# PulseOxi.net
KiCad netlist of a schematic drawn in EAGLE
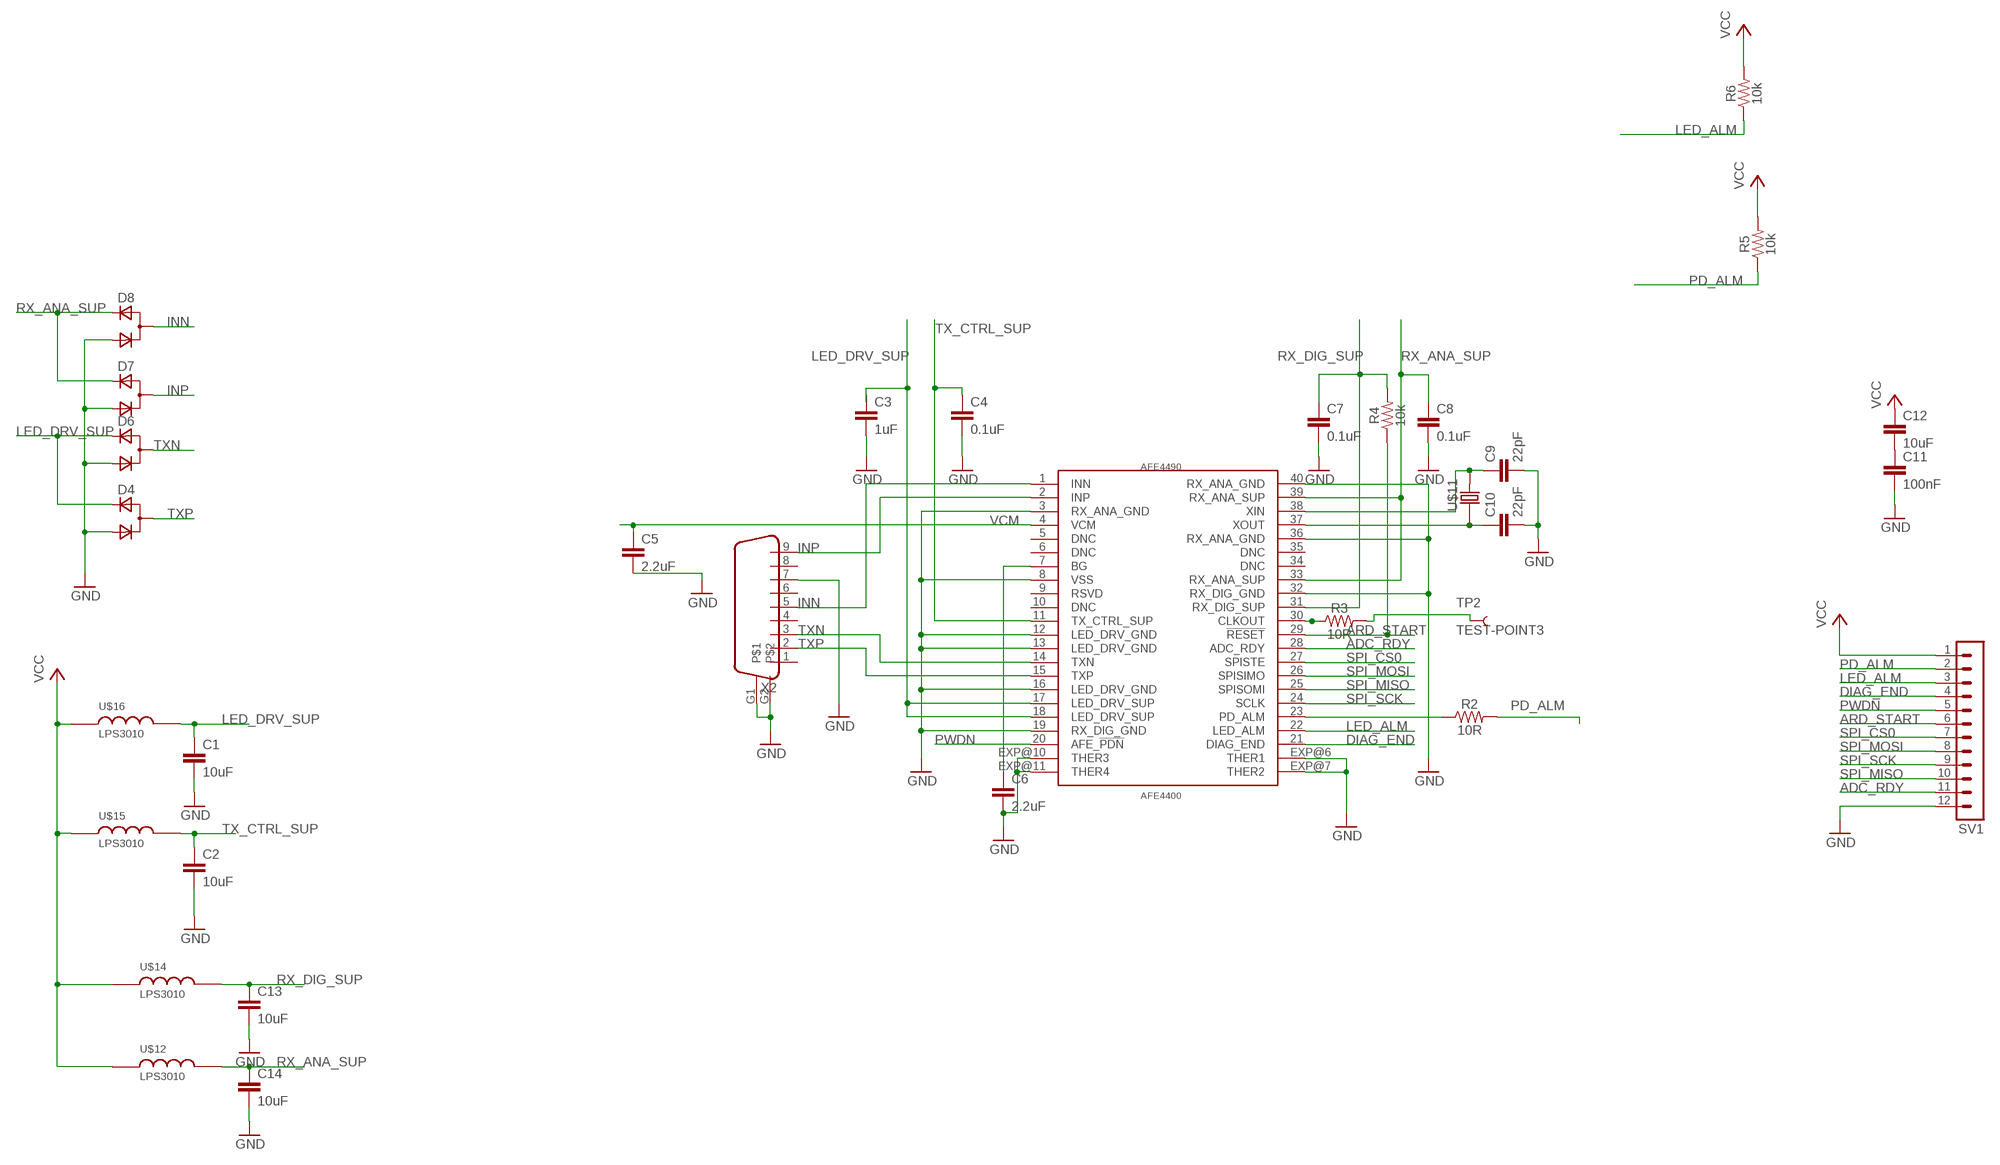
[diagram p0: schematic, sheet 1]

(export (version "E")
  (design (tool "Eeschema 10.0.6"))
  (components
    (comp (ref "AFE4490")
      (value "AFE4400")
      (footprint "eagle-import:QFN-40")
      (libsource (lib "eagle-import") (part "AFE4400"))
    )
    (comp (ref "C1")
      (value "10uF")
      (footprint "eagle-import:0603")
      (libsource (lib "eagle-import") (part "27PF-0603-50V-5%"))
    )
    (comp (ref "C2")
      (value "10uF")
      (footprint "eagle-import:0603")
      (libsource (lib "eagle-import") (part "27PF-0603-50V-5%"))
    )
    (comp (ref "C3")
      (value "1uF")
      (footprint "eagle-import:0603")
      (libsource (lib "eagle-import") (part "27PF-0603-50V-5%"))
    )
    (comp (ref "C4")
      (value "0.1uF")
      (footprint "eagle-import:0603")
      (libsource (lib "eagle-import") (part "27PF-0603-50V-5%"))
    )
    (comp (ref "C5")
      (value "2.2uF")
      (footprint "eagle-import:0603")
      (libsource (lib "eagle-import") (part "27PF-0603-50V-5%"))
    )
    (comp (ref "C6")
      (value "2.2uF")
      (footprint "eagle-import:0603")
      (libsource (lib "eagle-import") (part "27PF-0603-50V-5%"))
    )
    (comp (ref "C7")
      (value "0.1uF")
      (footprint "eagle-import:0603")
      (libsource (lib "eagle-import") (part "27PF-0603-50V-5%"))
    )
    (comp (ref "C8")
      (value "0.1uF")
      (footprint "eagle-import:0603")
      (libsource (lib "eagle-import") (part "27PF-0603-50V-5%"))
    )
    (comp (ref "C9")
      (value "22pF")
      (footprint "eagle-import:0603")
      (libsource (lib "eagle-import") (part "27PF-0603-50V-5%"))
    )
    (comp (ref "C10")
      (value "22pF")
      (footprint "eagle-import:0603")
      (libsource (lib "eagle-import") (part "27PF-0603-50V-5%"))
    )
    (comp (ref "C11")
      (value "100nF")
      (footprint "eagle-import:0603")
      (libsource (lib "eagle-import") (part "27PF-0603-50V-5%"))
    )
    (comp (ref "C12")
      (value "10uF")
      (footprint "eagle-import:0603")
      (libsource (lib "eagle-import") (part "27PF-0603-50V-5%"))
    )
    (comp (ref "C13")
      (value "10uF")
      (footprint "eagle-import:0603")
      (libsource (lib "eagle-import") (part "27PF-0603-50V-5%"))
    )
    (comp (ref "C14")
      (value "10uF")
      (footprint "eagle-import:0603")
      (libsource (lib "eagle-import") (part "27PF-0603-50V-5%"))
    )
    (comp (ref "D4")
      (value "D_ACACSOT323")
      (footprint "eagle-import:SOT323")
      (libsource (lib "eagle-import") (part "D_ACACSOT323"))
    )
    (comp (ref "D6")
      (value "D_ACACSOT323")
      (footprint "eagle-import:SOT323")
      (libsource (lib "eagle-import") (part "D_ACACSOT323"))
    )
    (comp (ref "D7")
      (value "D_ACACSOT323")
      (footprint "eagle-import:SOT323")
      (libsource (lib "eagle-import") (part "D_ACACSOT323"))
    )
    (comp (ref "D8")
      (value "D_ACACSOT323")
      (footprint "eagle-import:SOT323")
      (libsource (lib "eagle-import") (part "D_ACACSOT323"))
    )
    (comp (ref "R2")
      (value "10R")
      (footprint "eagle-import:0603")
      (libsource (lib "eagle-import") (part "1.8MOHM"))
    )
    (comp (ref "R3")
      (value "10R")
      (footprint "eagle-import:0603")
      (libsource (lib "eagle-import") (part "1.8MOHM"))
    )
    (comp (ref "R4")
      (value "10k")
      (footprint "eagle-import:0603")
      (libsource (lib "eagle-import") (part "1.8MOHM"))
    )
    (comp (ref "R5")
      (value "10k")
      (footprint "eagle-import:0603")
      (libsource (lib "eagle-import") (part "1.8MOHM"))
    )
    (comp (ref "R6")
      (value "10k")
      (footprint "eagle-import:0603")
      (libsource (lib "eagle-import") (part "1.8MOHM"))
    )
    (comp (ref "SV1")
      (value "MA12-1")
      (footprint "eagle-import:MA12-1")
      (libsource (lib "eagle-import") (part "MA12-1"))
    )
    (comp (ref "TP2")
      (value "TEST-POINT3")
      (footprint "eagle-import:PAD.03X.03")
      (libsource (lib "eagle-import") (part "TEST-POINT3"))
    )
    (comp (ref "U$11")
      (value "ABM3")
      (footprint "eagle-import:ABM3")
      (libsource (lib "eagle-import") (part "ABM3"))
    )
    (comp (ref "U$12")
      (value "LPS3010")
      (footprint "eagle-import:LPS")
      (libsource (lib "eagle-import") (part "LPS"))
    )
    (comp (ref "U$14")
      (value "LPS3010")
      (footprint "eagle-import:LPS")
      (libsource (lib "eagle-import") (part "LPS"))
    )
    (comp (ref "U$15")
      (value "LPS3010")
      (footprint "eagle-import:LPS")
      (libsource (lib "eagle-import") (part "LPS"))
    )
    (comp (ref "U$16")
      (value "LPS3010")
      (footprint "eagle-import:LPS")
      (libsource (lib "eagle-import") (part "LPS"))
    )
    (comp (ref "X2")
      (value "DB9")
      (footprint "eagle-import:DB9")
      (libsource (lib "eagle-import") (part "DB9"))
    )
  )
  (nets
    (net (code "1") (name "/ADC_RDY") (class "Default")
      (node (ref "AFE4490") (pin "28") (pinfunction "ADC_RDY_28") (pintype "bidirectional"))
      (node (ref "SV1") (pin "11") (pinfunction "11_11") (pintype "passive"))
    )
    (net (code "2") (name "/ARD_START") (class "Default")
      (node (ref "AFE4490") (pin "29") (pinfunction "~{RESET}_29") (pintype "bidirectional"))
      (node (ref "R4") (pin "1") (pinfunction "1_1") (pintype "passive"))
      (node (ref "SV1") (pin "6") (pinfunction "6_6") (pintype "passive"))
    )
    (net (code "3") (name "/DIAG_END") (class "Default")
      (node (ref "AFE4490") (pin "21") (pinfunction "DIAG_END_21") (pintype "bidirectional"))
      (node (ref "SV1") (pin "4") (pinfunction "4_4") (pintype "passive"))
    )
    (net (code "4") (name "/INN") (class "Default")
      (node (ref "AFE4490") (pin "1") (pinfunction "INN_1") (pintype "bidirectional"))
      (node (ref "D8") (pin "1") (pinfunction "CA_1") (pintype "passive"))
      (node (ref "X2") (pin "5") (pinfunction "5_5") (pintype "passive"))
    )
    (net (code "5") (name "/INP") (class "Default")
      (node (ref "AFE4490") (pin "2") (pinfunction "INP_2") (pintype "bidirectional"))
      (node (ref "D7") (pin "1") (pinfunction "CA_1") (pintype "passive"))
      (node (ref "X2") (pin "9") (pinfunction "9_9") (pintype "passive"))
    )
    (net (code "6") (name "/LED_ALM") (class "Default")
      (node (ref "AFE4490") (pin "22") (pinfunction "LED_ALM_22") (pintype "bidirectional"))
      (node (ref "R6") (pin "1") (pinfunction "1_1") (pintype "passive"))
      (node (ref "SV1") (pin "3") (pinfunction "3_3") (pintype "passive"))
    )
    (net (code "7") (name "/LED_DRV_SUP") (class "Default")
      (node (ref "AFE4490") (pin "17") (pinfunction "LED_DRV_SUP_17") (pintype "bidirectional"))
      (node (ref "AFE4490") (pin "18") (pinfunction "LED_DRV_SUP_18") (pintype "bidirectional"))
      (node (ref "C1") (pin "1") (pinfunction "1_1") (pintype "passive"))
      (node (ref "C3") (pin "1") (pinfunction "1_1") (pintype "passive"))
      (node (ref "D4") (pin "3") (pinfunction "A_3") (pintype "passive"))
      (node (ref "D6") (pin "3") (pinfunction "A_3") (pintype "passive"))
      (node (ref "U$16") (pin "2") (pinfunction "P$2_2") (pintype "bidirectional"))
    )
    (net (code "8") (name "/PD_ALM") (class "Default")
      (node (ref "R2") (pin "2") (pinfunction "2_2") (pintype "passive"))
      (node (ref "R5") (pin "1") (pinfunction "1_1") (pintype "passive"))
      (node (ref "SV1") (pin "2") (pinfunction "2_2") (pintype "passive"))
    )
    (net (code "9") (name "/PWDN") (class "Default")
      (node (ref "AFE4490") (pin "20") (pinfunction "AFE_~{PDN}_20") (pintype "bidirectional"))
      (node (ref "SV1") (pin "5") (pinfunction "5_5") (pintype "passive"))
    )
    (net (code "10") (name "/RX_ANA_SUP") (class "Default")
      (node (ref "AFE4490") (pin "33") (pinfunction "RX_ANA_SUP_33") (pintype "bidirectional"))
      (node (ref "AFE4490") (pin "39") (pinfunction "RX_ANA_SUP_39") (pintype "bidirectional"))
      (node (ref "C14") (pin "1") (pinfunction "1_1") (pintype "passive"))
      (node (ref "C8") (pin "1") (pinfunction "1_1") (pintype "passive"))
      (node (ref "D7") (pin "3") (pinfunction "A_3") (pintype "passive"))
      (node (ref "D8") (pin "3") (pinfunction "A_3") (pintype "passive"))
      (node (ref "U$12") (pin "2") (pinfunction "P$2_2") (pintype "bidirectional"))
    )
    (net (code "11") (name "/RX_DIG_SUP") (class "Default")
      (node (ref "AFE4490") (pin "31") (pinfunction "RX_DIG_SUP_31") (pintype "bidirectional"))
      (node (ref "C13") (pin "1") (pinfunction "1_1") (pintype "passive"))
      (node (ref "C7") (pin "1") (pinfunction "1_1") (pintype "passive"))
      (node (ref "R4") (pin "2") (pinfunction "2_2") (pintype "passive"))
      (node (ref "U$14") (pin "2") (pinfunction "P$2_2") (pintype "bidirectional"))
    )
    (net (code "12") (name "/SPI_CS0") (class "Default")
      (node (ref "AFE4490") (pin "27") (pinfunction "SPISTE_27") (pintype "bidirectional"))
      (node (ref "SV1") (pin "7") (pinfunction "7_7") (pintype "passive"))
    )
    (net (code "13") (name "/SPI_MISO") (class "Default")
      (node (ref "AFE4490") (pin "25") (pinfunction "SPISOMI_25") (pintype "bidirectional"))
      (node (ref "SV1") (pin "10") (pinfunction "10_10") (pintype "passive"))
    )
    (net (code "14") (name "/SPI_MOSI") (class "Default")
      (node (ref "AFE4490") (pin "26") (pinfunction "SPISIMO_26") (pintype "bidirectional"))
      (node (ref "SV1") (pin "8") (pinfunction "8_8") (pintype "passive"))
    )
    (net (code "15") (name "/SPI_SCK") (class "Default")
      (node (ref "AFE4490") (pin "24") (pinfunction "SCLK_24") (pintype "bidirectional"))
      (node (ref "SV1") (pin "9") (pinfunction "9_9") (pintype "passive"))
    )
    (net (code "16") (name "/TXN") (class "Default")
      (node (ref "AFE4490") (pin "14") (pinfunction "TXN_14") (pintype "bidirectional"))
      (node (ref "D6") (pin "1") (pinfunction "CA_1") (pintype "passive"))
      (node (ref "X2") (pin "3") (pinfunction "3_3") (pintype "passive"))
    )
    (net (code "17") (name "/TXP") (class "Default")
      (node (ref "AFE4490") (pin "15") (pinfunction "TXP_15") (pintype "bidirectional"))
      (node (ref "D4") (pin "1") (pinfunction "CA_1") (pintype "passive"))
      (node (ref "X2") (pin "2") (pinfunction "2_2") (pintype "passive"))
    )
    (net (code "18") (name "/TX_CTRL_SUP") (class "Default")
      (node (ref "AFE4490") (pin "11") (pinfunction "TX_CTRL_SUP_11") (pintype "bidirectional"))
      (node (ref "C2") (pin "1") (pinfunction "1_1") (pintype "passive"))
      (node (ref "C4") (pin "1") (pinfunction "1_1") (pintype "passive"))
      (node (ref "U$15") (pin "2") (pinfunction "P$2_2") (pintype "bidirectional"))
    )
    (net (code "19") (name "/VCM") (class "Default")
      (node (ref "AFE4490") (pin "4") (pinfunction "VCM_4") (pintype "bidirectional"))
      (node (ref "C5") (pin "1") (pinfunction "1_1") (pintype "passive"))
    )
    (net (code "20") (name "GND") (class "Default")
      (node (ref "AFE4490") (pin "12") (pinfunction "LED_DRV_GND_12") (pintype "bidirectional"))
      (node (ref "AFE4490") (pin "13") (pinfunction "LED_DRV_GND_13") (pintype "bidirectional"))
      (node (ref "AFE4490") (pin "16") (pinfunction "LED_DRV_GND_16") (pintype "bidirectional"))
      (node (ref "AFE4490") (pin "19") (pinfunction "RX_DIG_GND_19") (pintype "bidirectional"))
      (node (ref "AFE4490") (pin "3") (pinfunction "RX_ANA_GND_3") (pintype "bidirectional"))
      (node (ref "AFE4490") (pin "32") (pinfunction "RX_DIG_GND_32") (pintype "bidirectional"))
      (node (ref "AFE4490") (pin "36") (pinfunction "RX_ANA_GND_36") (pintype "bidirectional"))
      (node (ref "AFE4490") (pin "40") (pinfunction "RX_ANA_GND_40") (pintype "bidirectional"))
      (node (ref "AFE4490") (pin "8") (pinfunction "VSS_8") (pintype "bidirectional"))
      (node (ref "AFE4490") (pin "EXP@10") (pinfunction "THER3_EXP@10") (pintype "bidirectional"))
      (node (ref "AFE4490") (pin "EXP@11") (pinfunction "THER4_EXP@11") (pintype "bidirectional"))
      (node (ref "AFE4490") (pin "EXP@6") (pinfunction "THER1_EXP@6") (pintype "bidirectional"))
      (node (ref "AFE4490") (pin "EXP@7") (pinfunction "THER2_EXP@7") (pintype "bidirectional"))
      (node (ref "C1") (pin "2") (pinfunction "2_2") (pintype "passive"))
      (node (ref "C10") (pin "2") (pinfunction "2_2") (pintype "passive"))
      (node (ref "C11") (pin "2") (pinfunction "2_2") (pintype "passive"))
      (node (ref "C13") (pin "2") (pinfunction "2_2") (pintype "passive"))
      (node (ref "C14") (pin "2") (pinfunction "2_2") (pintype "passive"))
      (node (ref "C2") (pin "2") (pinfunction "2_2") (pintype "passive"))
      (node (ref "C3") (pin "2") (pinfunction "2_2") (pintype "passive"))
      (node (ref "C4") (pin "2") (pinfunction "2_2") (pintype "passive"))
      (node (ref "C5") (pin "2") (pinfunction "2_2") (pintype "passive"))
      (node (ref "C6") (pin "2") (pinfunction "2_2") (pintype "passive"))
      (node (ref "C7") (pin "2") (pinfunction "2_2") (pintype "passive"))
      (node (ref "C8") (pin "2") (pinfunction "2_2") (pintype "passive"))
      (node (ref "C9") (pin "2") (pinfunction "2_2") (pintype "passive"))
      (node (ref "D4") (pin "2") (pinfunction "C_2") (pintype "passive"))
      (node (ref "D6") (pin "2") (pinfunction "C_2") (pintype "passive"))
      (node (ref "D7") (pin "2") (pinfunction "C_2") (pintype "passive"))
      (node (ref "D8") (pin "2") (pinfunction "C_2") (pintype "passive"))
      (node (ref "SV1") (pin "12") (pinfunction "12_12") (pintype "passive"))
      (node (ref "X2") (pin "7") (pinfunction "7_7") (pintype "passive"))
      (node (ref "X2") (pin "G1") (pinfunction "P$1_G1") (pintype "bidirectional"))
      (node (ref "X2") (pin "G2") (pinfunction "P$2_G2") (pintype "bidirectional"))
    )
    (net (code "21") (name "Net-(AFE4490-BG)") (class "Default")
      (node (ref "AFE4490") (pin "7") (pinfunction "BG_7") (pintype "bidirectional"))
      (node (ref "C6") (pin "1") (pinfunction "1_1") (pintype "passive"))
    )
    (net (code "22") (name "Net-(AFE4490-CLKOUT)") (class "Default")
      (node (ref "AFE4490") (pin "30") (pinfunction "CLKOUT_30") (pintype "bidirectional"))
      (node (ref "R3") (pin "1") (pinfunction "1_1") (pintype "passive"))
    )
    (net (code "23") (name "Net-(AFE4490-PD_ALM)") (class "Default")
      (node (ref "AFE4490") (pin "23") (pinfunction "PD_ALM_23") (pintype "bidirectional"))
      (node (ref "R2") (pin "1") (pinfunction "1_1") (pintype "passive"))
    )
    (net (code "24") (name "Net-(AFE4490-XIN)") (class "Default")
      (node (ref "AFE4490") (pin "38") (pinfunction "XIN_38") (pintype "bidirectional"))
      (node (ref "C9") (pin "1") (pinfunction "1_1") (pintype "passive"))
      (node (ref "U$11") (pin "2") (pinfunction "2_2") (pintype "passive"))
    )
    (net (code "25") (name "Net-(AFE4490-XOUT)") (class "Default")
      (node (ref "AFE4490") (pin "37") (pinfunction "XOUT_37") (pintype "bidirectional"))
      (node (ref "C10") (pin "1") (pinfunction "1_1") (pintype "passive"))
      (node (ref "U$11") (pin "1") (pinfunction "1_1") (pintype "passive"))
    )
    (net (code "26") (name "Net-(C11-Pad1)") (class "Default")
      (node (ref "C11") (pin "1") (pinfunction "1_1") (pintype "passive"))
      (node (ref "C12") (pin "2") (pinfunction "2_2") (pintype "passive"))
    )
    (net (code "27") (name "Net-(TP2-1)") (class "Default")
      (node (ref "R3") (pin "2") (pinfunction "2_2") (pintype "passive"))
      (node (ref "TP2") (pin "P$1") (pinfunction "1_P$1") (pintype "bidirectional"))
    )
    (net (code "28") (name "VCC") (class "Default")
      (node (ref "C12") (pin "1") (pinfunction "1_1") (pintype "passive"))
      (node (ref "R5") (pin "2") (pinfunction "2_2") (pintype "passive"))
      (node (ref "R6") (pin "2") (pinfunction "2_2") (pintype "passive"))
      (node (ref "SV1") (pin "1") (pinfunction "1_1") (pintype "passive"))
      (node (ref "U$12") (pin "1") (pinfunction "P$1_1") (pintype "bidirectional"))
      (node (ref "U$14") (pin "1") (pinfunction "P$1_1") (pintype "bidirectional"))
      (node (ref "U$15") (pin "1") (pinfunction "P$1_1") (pintype "bidirectional"))
      (node (ref "U$16") (pin "1") (pinfunction "P$1_1") (pintype "bidirectional"))
    )
    (net (code "29") (name "unconnected-(AFE4490-DNC-Pad5)") (class "Default")
      (node (ref "AFE4490") (pin "5") (pinfunction "DNC_5") (pintype "bidirectional"))
    )
    (net (code "30") (name "unconnected-(AFE4490-DNC-Pad6)") (class "Default")
      (node (ref "AFE4490") (pin "6") (pinfunction "DNC_6") (pintype "bidirectional"))
    )
    (net (code "31") (name "unconnected-(AFE4490-DNC-Pad10)") (class "Default")
      (node (ref "AFE4490") (pin "10") (pinfunction "DNC_10") (pintype "bidirectional"))
    )
    (net (code "32") (name "unconnected-(AFE4490-DNC-Pad34)") (class "Default")
      (node (ref "AFE4490") (pin "34") (pinfunction "DNC_34") (pintype "bidirectional"))
    )
    (net (code "33") (name "unconnected-(AFE4490-DNC-Pad35)") (class "Default")
      (node (ref "AFE4490") (pin "35") (pinfunction "DNC_35") (pintype "bidirectional"))
    )
    (net (code "34") (name "unconnected-(AFE4490-RSVD-Pad9)") (class "Default")
      (node (ref "AFE4490") (pin "9") (pinfunction "RSVD_9") (pintype "bidirectional"))
    )
    (net (code "35") (name "unconnected-(X2-Pad1)") (class "Default")
      (node (ref "X2") (pin "1") (pinfunction "1_1") (pintype "passive"))
    )
    (net (code "36") (name "unconnected-(X2-Pad4)") (class "Default")
      (node (ref "X2") (pin "4") (pinfunction "4_4") (pintype "passive"))
    )
    (net (code "37") (name "unconnected-(X2-Pad6)") (class "Default")
      (node (ref "X2") (pin "6") (pinfunction "6_6") (pintype "passive"))
    )
    (net (code "38") (name "unconnected-(X2-Pad8)") (class "Default")
      (node (ref "X2") (pin "8") (pinfunction "8_8") (pintype "passive"))
    )
  )
)
